# Power.net
KiCad netlist of a schematic drawn in Altium Designer
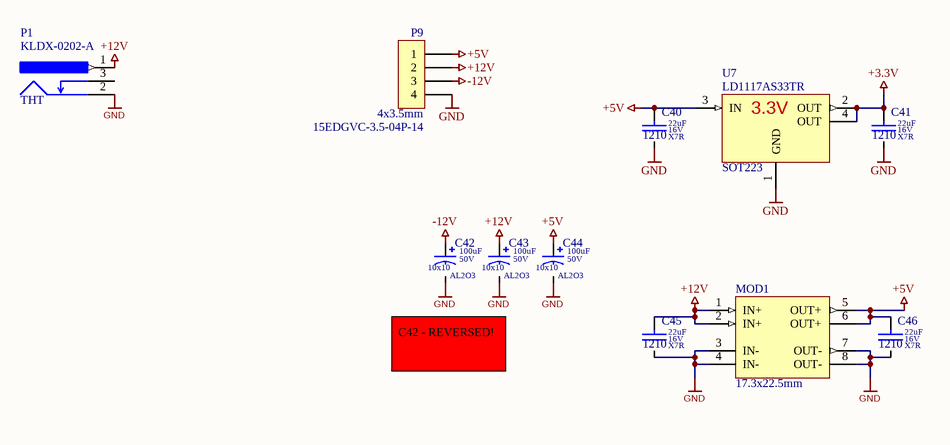
[diagram p0: Power.SchDoc]

(export (version "E")
  (design (tool "Eeschema 10.0.6"))
  (components
    (comp (ref "C40")
      (value "22uF")
      (footprint "C_1210_3225")
      (description "Capacitor")
      (fields
        (field (name "DIELECTRIC") "X7R")
        (field (name "VOLTAGE") "16V")
        (field (name "SCH_FOOTPRINT") "1210")
        (field (name "PART NUMBER") "C_22uF_16V_X7R_1210_10_AECQ1")
        (field (name "MANUFACTURER") "Murata")
      )
      (libsource (lib "Library") (part "C"))
    )
    (comp (ref "C41")
      (value "22uF")
      (footprint "C_1210_3225")
      (description "Capacitor")
      (fields
        (field (name "DIELECTRIC") "X7R")
        (field (name "VOLTAGE") "16V")
        (field (name "SCH_FOOTPRINT") "1210")
        (field (name "PART NUMBER") "C_22uF_16V_X7R_1210_10_AECQ1")
        (field (name "MANUFACTURER") "Murata")
      )
      (libsource (lib "Library") (part "C"))
    )
    (comp (ref "C42")
      (value "100uF")
      (footprint "CE_D_10x10_SMD")
      (description "Polarized Capacitor")
      (fields
        (field (name "DIELECTRIC") "AL2O3")
        (field (name "SCH_FOOTPRINT") "10x10")
        (field (name "VOLTAGE") "50V")
        (field (name "PART NUMBER") "CE_100uF_50V_AL2O3_10x10_20")
        (field (name "MANUFACTURER") "Nichicon")
      )
      (libsource (lib "Library") (part "CE"))
    )
    (comp (ref "C43")
      (value "100uF")
      (footprint "CE_D_10x10_SMD")
      (description "Polarized Capacitor")
      (fields
        (field (name "DIELECTRIC") "AL2O3")
        (field (name "SCH_FOOTPRINT") "10x10")
        (field (name "VOLTAGE") "50V")
        (field (name "PART NUMBER") "CE_100uF_50V_AL2O3_10x10_20")
        (field (name "MANUFACTURER") "Nichicon")
      )
      (libsource (lib "Library") (part "CE"))
    )
    (comp (ref "C44")
      (value "100uF")
      (footprint "CE_D_10x10_SMD")
      (description "Polarized Capacitor")
      (fields
        (field (name "DIELECTRIC") "AL2O3")
        (field (name "SCH_FOOTPRINT") "10x10")
        (field (name "VOLTAGE") "50V")
        (field (name "PART NUMBER") "CE_100uF_50V_AL2O3_10x10_20")
        (field (name "MANUFACTURER") "Nichicon")
      )
      (libsource (lib "Library") (part "CE"))
    )
    (comp (ref "C45")
      (value "22uF")
      (footprint "C_1210_3225")
      (description "Capacitor")
      (fields
        (field (name "DIELECTRIC") "X7R")
        (field (name "VOLTAGE") "16V")
        (field (name "SCH_FOOTPRINT") "1210")
        (field (name "PART NUMBER") "C_22uF_16V_X7R_1210_10_AECQ1")
        (field (name "MANUFACTURER") "Murata")
      )
      (libsource (lib "Library") (part "C"))
    )
    (comp (ref "C46")
      (value "22uF")
      (footprint "C_1210_3225")
      (description "Capacitor")
      (fields
        (field (name "DIELECTRIC") "X7R")
        (field (name "VOLTAGE") "16V")
        (field (name "SCH_FOOTPRINT") "1210")
        (field (name "PART NUMBER") "C_22uF_16V_X7R_1210_10_AECQ1")
        (field (name "MANUFACTURER") "Murata")
      )
      (libsource (lib "Library") (part "C"))
    )
    (comp (ref "MOD1")
      (value "Low cost, Aliexpress-ready DC-DC buck converter using MP1584")
      (footprint "MOD_BUCK_MP1584")
      (fields (field (name "SCH_FOOTPRINT") "17.3x22.5mm") (field (name "PART NUMBER") "MOD_BUCK_MP1584"))
      (libsource (lib "Library") (part "MOD_BUCK_MP1584"))
    )
    (comp (ref "P1")
      (value "KLDX-0202-A")
      (footprint "P_KLDX-0202-A")
      (description "Typical 3-pin jack power connector with switch")
      (fields
        (field (name "SCH_FOOTPRINT") "THT")
        (field (name "PART NUMBER") "P_KLDX-0202-A")
        (field (name "MANUFACTURER") "Kycon")
      )
      (libsource (lib "Library") (part "P_DC_JACK"))
    )
    (comp (ref "P9")
      (value "15EDGVC-3.5-04P-14")
      (footprint "P_15EDGVC-3.5-04P-14")
      (description "Pin Header")
      (fields
        (field (name "SCH_FOOTPRINT") "4x3.5mm")
        (field (name "PART NUMBER") "P_15EDGVC-3.5-04P-14")
        (field (name "MANUFACTURER") "DEGSON ELECTRONICS")
      )
      (libsource (lib "Library") (part "P_HEADER_1x4"))
    )
    (comp (ref "U7")
      (value "LD1117AS33TR")
      (footprint "SOT223_SC73")
      (description "typical configuration")
      (fields
        (field (name "SCH_FOOTPRINT") "SOT223")
        (field (name "PART NUMBER") "VL_LD1117AS33TR_3V3_1A2")
        (field (name "VOLTAGE") "3.3V")
      )
      (libsource (lib "Library") (part "VL_4pin_3_1_2,4"))
    )
  )
  (nets
    (net (code "1") (name "+3.3V") (class "Default")
      (node (ref "C41") (pin "1") (pinfunction "1_1") (pintype "passive"))
      (node (ref "U7") (pin "2") (pinfunction "OUT_2") (pintype "output"))
      (node (ref "U7") (pin "4") (pinfunction "OUT_4") (pintype "power_in"))
    )
    (net (code "2") (name "+5V") (class "Default")
      (node (ref "C40") (pin "1") (pinfunction "1_1") (pintype "passive"))
      (node (ref "C44") (pin "1") (pinfunction "1_1") (pintype "passive"))
      (node (ref "C46") (pin "1") (pinfunction "1_1") (pintype "passive"))
      (node (ref "MOD1") (pin "5") (pinfunction "OUT+_5") (pintype "output"))
      (node (ref "MOD1") (pin "6") (pinfunction "OUT+_6") (pintype "passive"))
      (node (ref "P9") (pin "1") (pinfunction "1_1") (pintype "passive"))
      (node (ref "U7") (pin "3") (pinfunction "IN_3") (pintype "input"))
    )
    (net (code "3") (name "+12V") (class "Default")
      (node (ref "C43") (pin "1") (pinfunction "1_1") (pintype "passive"))
      (node (ref "C45") (pin "1") (pinfunction "1_1") (pintype "passive"))
      (node (ref "MOD1") (pin "1") (pinfunction "IN+_1") (pintype "input"))
      (node (ref "MOD1") (pin "2") (pinfunction "IN+_2") (pintype "input"))
      (node (ref "P1") (pin "1") (pinfunction "1_1") (pintype "output"))
      (node (ref "P9") (pin "2") (pinfunction "2_2") (pintype "passive"))
    )
    (net (code "4") (name "-12V") (class "Default")
      (node (ref "C42") (pin "1") (pinfunction "1_1") (pintype "passive"))
      (node (ref "P9") (pin "3") (pinfunction "3_3") (pintype "passive"))
    )
    (net (code "5") (name "GND") (class "Default")
      (node (ref "C40") (pin "2") (pinfunction "2_2") (pintype "passive"))
      (node (ref "C41") (pin "2") (pinfunction "2_2") (pintype "passive"))
      (node (ref "C42") (pin "2") (pinfunction "2_2") (pintype "passive"))
      (node (ref "C43") (pin "2") (pinfunction "2_2") (pintype "passive"))
      (node (ref "C44") (pin "2") (pinfunction "2_2") (pintype "passive"))
      (node (ref "C45") (pin "2") (pinfunction "2_2") (pintype "passive"))
      (node (ref "C46") (pin "2") (pinfunction "2_2") (pintype "passive"))
      (node (ref "MOD1") (pin "3") (pinfunction "IN-_3") (pintype "power_in"))
      (node (ref "MOD1") (pin "4") (pinfunction "IN-_4") (pintype "power_in"))
      (node (ref "MOD1") (pin "7") (pinfunction "OUT-_7") (pintype "output"))
      (node (ref "MOD1") (pin "8") (pinfunction "OUT-_8") (pintype "passive"))
      (node (ref "P1") (pin "2") (pinfunction "2_2") (pintype "passive"))
      (node (ref "P9") (pin "4") (pinfunction "4_4") (pintype "passive"))
      (node (ref "U7") (pin "1") (pinfunction "GND_1") (pintype "power_in"))
    )
    (net (code "6") (name "unconnected-(P1-Pad3)") (class "Default")
      (node (ref "P1") (pin "3") (pinfunction "3_3") (pintype "passive"))
    )
  )
)
